# PCIE_Connector.net
KiCad netlist of a schematic drawn in Altium Designer
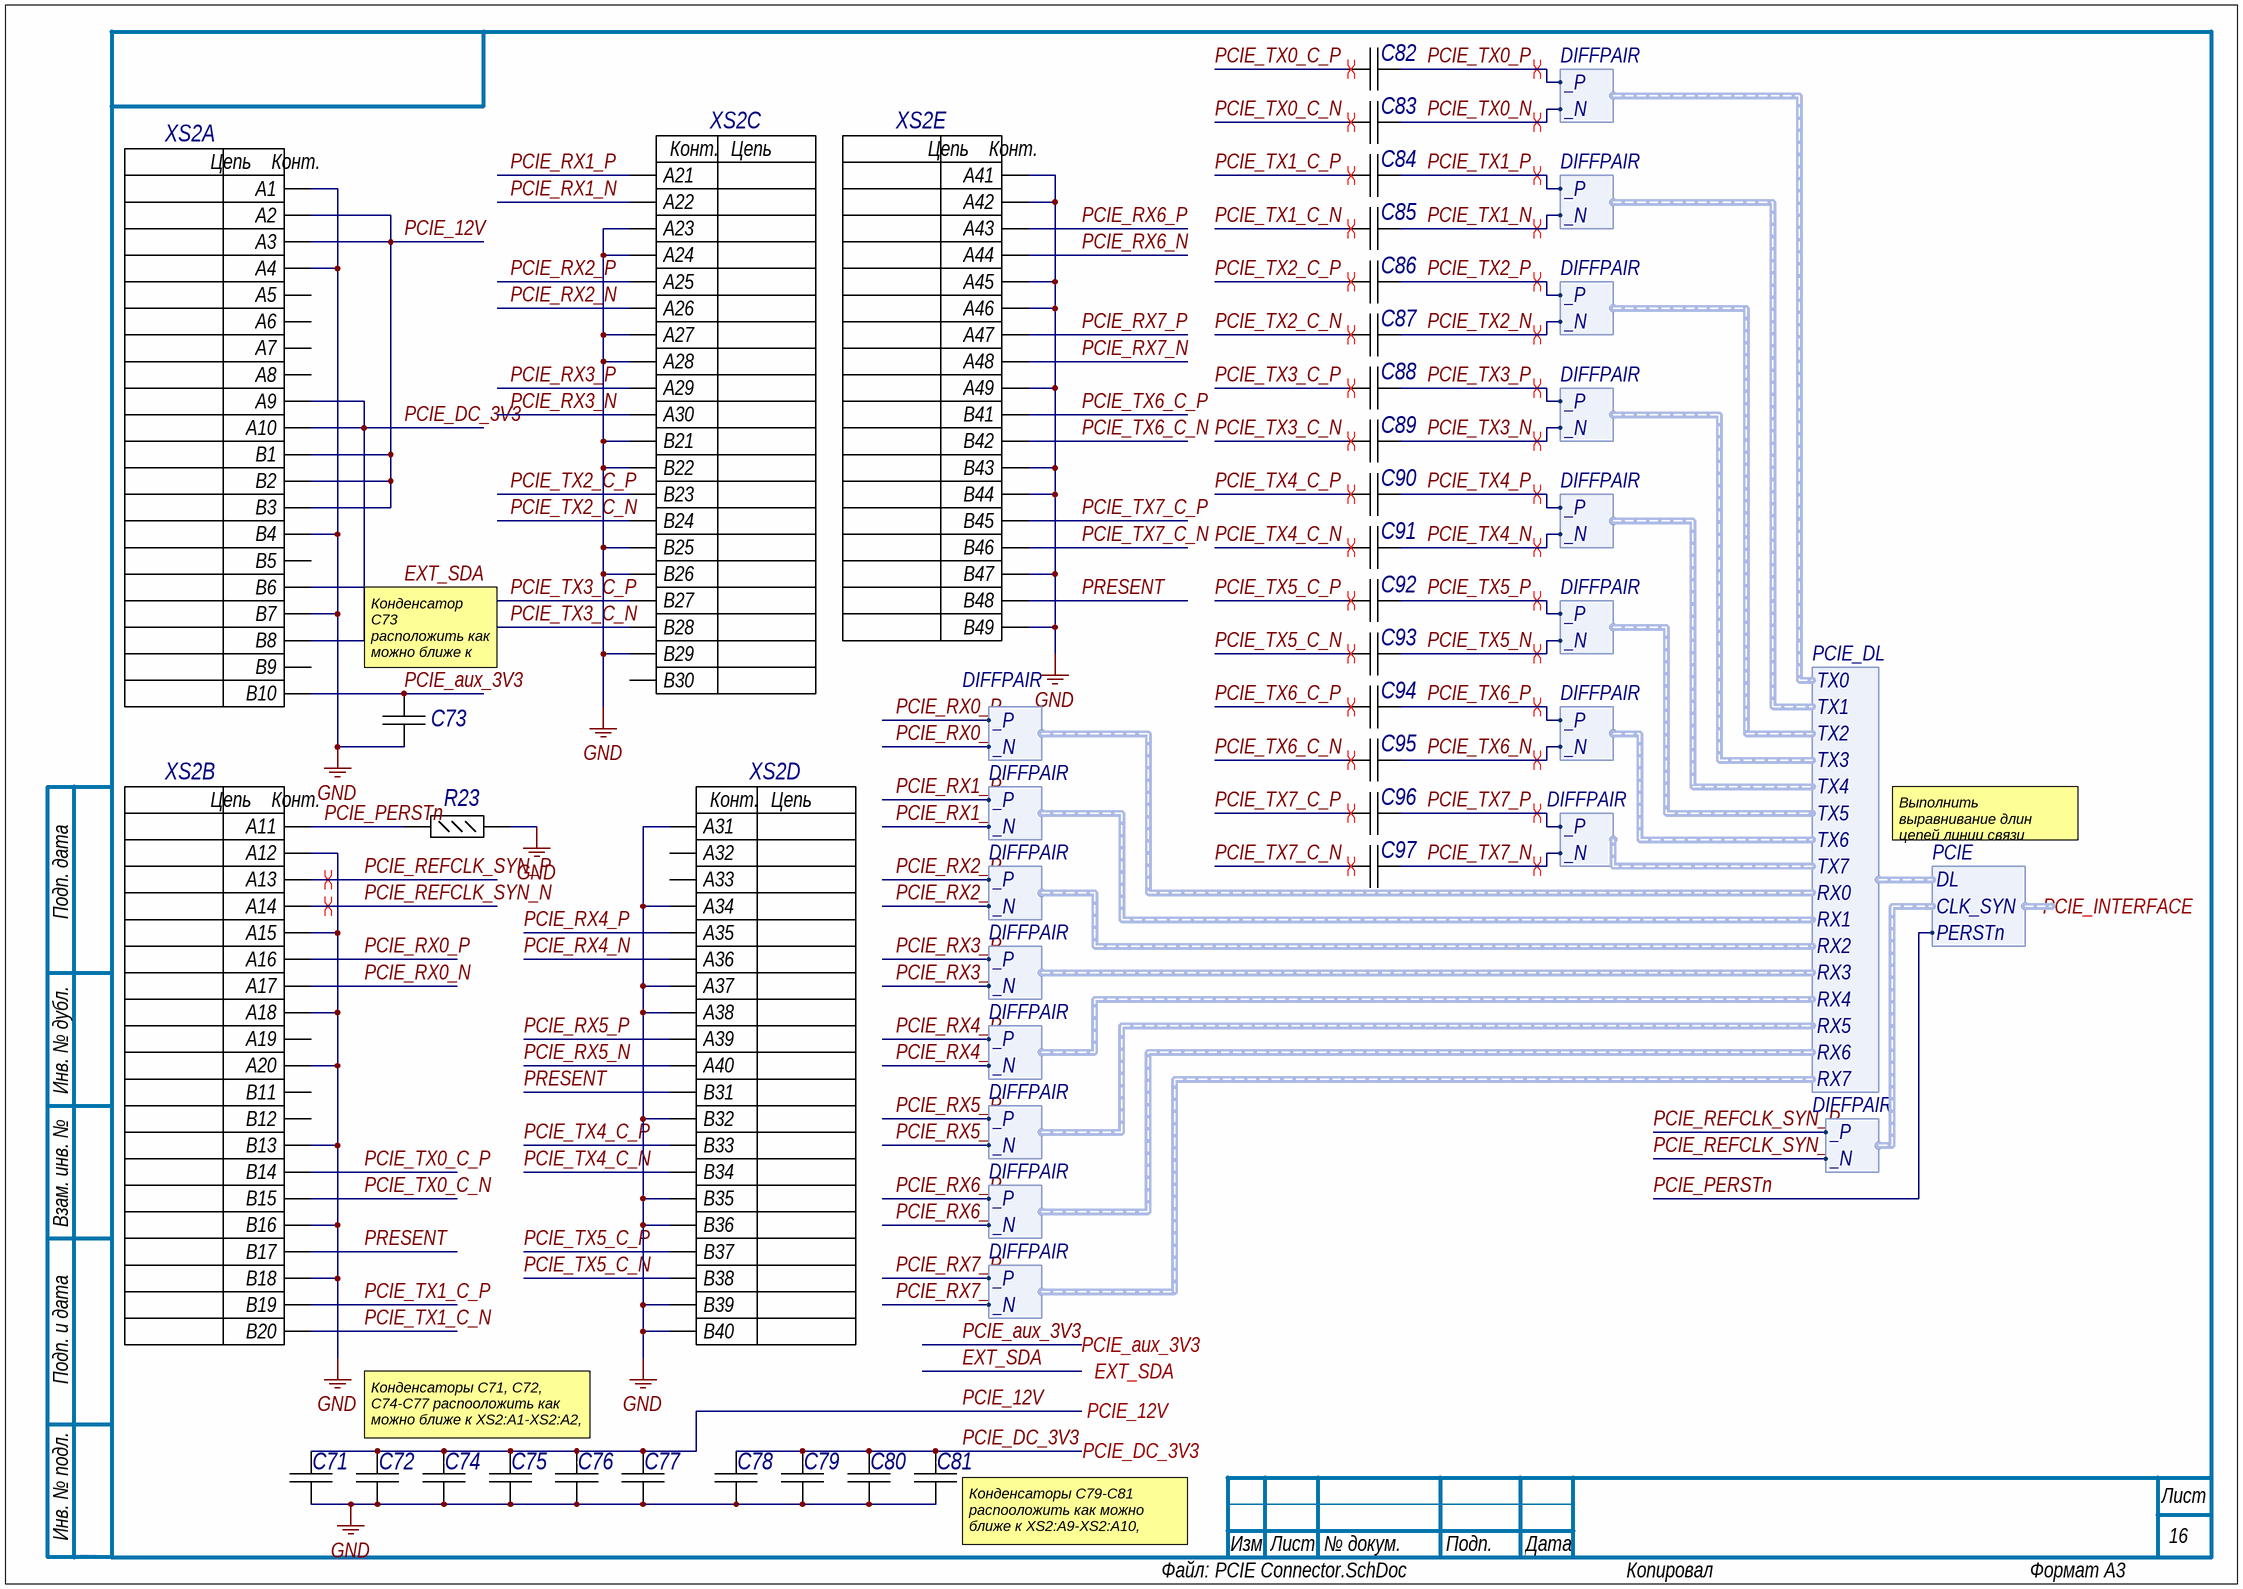
[diagram p0: PCIE Connector.SchDoc]

(export (version "E")
  (design (tool "Eeschema 10.0.6"))
  (components
    (comp (ref "C71")
      (value "GRM31CR61E226KE15L")
      (footprint "CAPC3216X180X55ML20T25")
      (description "Chip Capacitor, 22 uF, +/- 10%, 25 V, -55 to 85 degC, 1206 (3216 Metric), RoHS, Tape and Reel")
      (fields (field (name "TOLERANCE") "10%"))
      (libsource (lib "MiniPC DB") (part "CAP_NP"))
    )
    (comp (ref "C72")
      (value "C1005X7R1E104M")
      (footprint "CAPC1005X55X10LL05")
      (description "Chip Capacitor, 0.1 uF, +/- 20%, 25 V, -55 to 125 degC, 0402 (1005 Metric), RoHS, Tape and Reel")
      (fields (field (name "TOLERANCE") "20%"))
      (libsource (lib "MiniPC DB") (part "CAP_NP"))
    )
    (comp (ref "C73")
      (value "C1005X7R1E104M")
      (footprint "CAPC1005X55X10LL05")
      (description "Chip Capacitor, 0.1 uF, +/- 20%, 25 V, -55 to 125 degC, 0402 (1005 Metric), RoHS, Tape and Reel")
      (fields (field (name "TOLERANCE") "20%"))
      (libsource (lib "MiniPC DB") (part "CAP_NP"))
    )
    (comp (ref "C74")
      (value "C1005X7R1E104M")
      (footprint "CAPC1005X55X10LL05")
      (description "Chip Capacitor, 0.1 uF, +/- 20%, 25 V, -55 to 125 degC, 0402 (1005 Metric), RoHS, Tape and Reel")
      (fields (field (name "TOLERANCE") "20%"))
      (libsource (lib "MiniPC DB") (part "CAP_NP"))
    )
    (comp (ref "C75")
      (value "C1005X7R1E104M")
      (footprint "CAPC1005X55X10LL05")
      (description "Chip Capacitor, 0.1 uF, +/- 20%, 25 V, -55 to 125 degC, 0402 (1005 Metric), RoHS, Tape and Reel")
      (fields (field (name "TOLERANCE") "20%"))
      (libsource (lib "MiniPC DB") (part "CAP_NP"))
    )
    (comp (ref "C76")
      (value "C1005X7R1E104M")
      (footprint "CAPC1005X55X10LL05")
      (description "Chip Capacitor, 0.1 uF, +/- 20%, 25 V, -55 to 125 degC, 0402 (1005 Metric), RoHS, Tape and Reel")
      (fields (field (name "TOLERANCE") "20%"))
      (libsource (lib "MiniPC DB") (part "CAP_NP"))
    )
    (comp (ref "C77")
      (value "C1005X7R1E104M")
      (footprint "CAPC1005X55X10LL05")
      (description "Chip Capacitor, 0.1 uF, +/- 20%, 25 V, -55 to 125 degC, 0402 (1005 Metric), RoHS, Tape and Reel")
      (fields (field (name "TOLERANCE") "20%"))
      (libsource (lib "MiniPC DB") (part "CAP_NP"))
    )
    (comp (ref "C78")
      (value "C1005X7R1E104M")
      (footprint "CAPC1005X55X10LL05")
      (description "Chip Capacitor, 0.1 uF, +/- 20%, 25 V, -55 to 125 degC, 0402 (1005 Metric), RoHS, Tape and Reel")
      (fields (field (name "TOLERANCE") "20%"))
      (libsource (lib "MiniPC DB") (part "CAP_NP"))
    )
    (comp (ref "C79")
      (value "C1005X7R1E104M")
      (footprint "CAPC1005X55X10LL05")
      (description "Chip Capacitor, 0.1 uF, +/- 20%, 25 V, -55 to 125 degC, 0402 (1005 Metric), RoHS, Tape and Reel")
      (fields (field (name "TOLERANCE") "20%"))
      (libsource (lib "MiniPC DB") (part "CAP_NP"))
    )
    (comp (ref "C80")
      (value "C1005X7R1E104M")
      (footprint "CAPC1005X55X10LL05")
      (description "Chip Capacitor, 0.1 uF, +/- 20%, 25 V, -55 to 125 degC, 0402 (1005 Metric), RoHS, Tape and Reel")
      (fields (field (name "TOLERANCE") "20%"))
      (libsource (lib "MiniPC DB") (part "CAP_NP"))
    )
    (comp (ref "C81")
      (value "GRM31CR60J107ME39L")
      (footprint "CAPC3216X190X55ML30T25")
      (description "Chip Capacitor, 100 uF, +/- 20%, 6.3 V, -55 to 85 degC, 1206 (3216 Metric), RoHS, Tape and Reel")
      (fields (field (name "TOLERANCE") "20%"))
      (libsource (lib "MiniPC DB") (part "CAP_NP"))
    )
    (comp (ref "C82")
      (value "GRM155R61A224KE19D")
      (footprint "CAPC1005X55X25NL05T10")
      (description "Chip Capacitor, 220 nF, +/- 10%, 10 V, -55 to 85 degC, 0402 (1005 Metric), RoHS, Tape and Reel")
      (fields (field (name "TOLERANCE") "10%") (field (name "MANUFACTURER") "Basic Passives"))
      (libsource (lib "MiniPC DB") (part "CAP_NP"))
    )
    (comp (ref "C83")
      (value "GRM155R61A224KE19D")
      (footprint "CAPC1005X55X25NL05T10")
      (description "Chip Capacitor, 220 nF, +/- 10%, 10 V, -55 to 85 degC, 0402 (1005 Metric), RoHS, Tape and Reel")
      (fields (field (name "TOLERANCE") "10%") (field (name "MANUFACTURER") "Basic Passives"))
      (libsource (lib "MiniPC DB") (part "CAP_NP"))
    )
    (comp (ref "C84")
      (value "GRM155R61A224KE19D")
      (footprint "CAPC1005X55X25NL05T10")
      (description "Chip Capacitor, 220 nF, +/- 10%, 10 V, -55 to 85 degC, 0402 (1005 Metric), RoHS, Tape and Reel")
      (fields (field (name "TOLERANCE") "10%") (field (name "MANUFACTURER") "Basic Passives"))
      (libsource (lib "MiniPC DB") (part "CAP_NP"))
    )
    (comp (ref "C85")
      (value "GRM155R61A224KE19D")
      (footprint "CAPC1005X55X25NL05T10")
      (description "Chip Capacitor, 220 nF, +/- 10%, 10 V, -55 to 85 degC, 0402 (1005 Metric), RoHS, Tape and Reel")
      (fields (field (name "TOLERANCE") "10%") (field (name "MANUFACTURER") "Basic Passives"))
      (libsource (lib "MiniPC DB") (part "CAP_NP"))
    )
    (comp (ref "C86")
      (value "GRM155R61A224KE19D")
      (footprint "CAPC1005X55X25NL05T10")
      (description "Chip Capacitor, 220 nF, +/- 10%, 10 V, -55 to 85 degC, 0402 (1005 Metric), RoHS, Tape and Reel")
      (fields (field (name "TOLERANCE") "10%") (field (name "MANUFACTURER") "Basic Passives"))
      (libsource (lib "MiniPC DB") (part "CAP_NP"))
    )
    (comp (ref "C87")
      (value "GRM155R61A224KE19D")
      (footprint "CAPC1005X55X25NL05T10")
      (description "Chip Capacitor, 220 nF, +/- 10%, 10 V, -55 to 85 degC, 0402 (1005 Metric), RoHS, Tape and Reel")
      (fields (field (name "TOLERANCE") "10%") (field (name "MANUFACTURER") "Basic Passives"))
      (libsource (lib "MiniPC DB") (part "CAP_NP"))
    )
    (comp (ref "C88")
      (value "GRM155R61A224KE19D")
      (footprint "CAPC1005X55X25NL05T10")
      (description "Chip Capacitor, 220 nF, +/- 10%, 10 V, -55 to 85 degC, 0402 (1005 Metric), RoHS, Tape and Reel")
      (fields (field (name "TOLERANCE") "10%") (field (name "MANUFACTURER") "Basic Passives"))
      (libsource (lib "MiniPC DB") (part "CAP_NP"))
    )
    (comp (ref "C89")
      (value "GRM155R61A224KE19D")
      (footprint "CAPC1005X55X25NL05T10")
      (description "Chip Capacitor, 220 nF, +/- 10%, 10 V, -55 to 85 degC, 0402 (1005 Metric), RoHS, Tape and Reel")
      (fields (field (name "TOLERANCE") "10%") (field (name "MANUFACTURER") "Basic Passives"))
      (libsource (lib "MiniPC DB") (part "CAP_NP"))
    )
    (comp (ref "C90")
      (value "GRM155R61A224KE19D")
      (footprint "CAPC1005X55X25NL05T10")
      (description "Chip Capacitor, 220 nF, +/- 10%, 10 V, -55 to 85 degC, 0402 (1005 Metric), RoHS, Tape and Reel")
      (fields (field (name "TOLERANCE") "10%") (field (name "MANUFACTURER") "Basic Passives"))
      (libsource (lib "MiniPC DB") (part "CAP_NP"))
    )
    (comp (ref "C91")
      (value "GRM155R61A224KE19D")
      (footprint "CAPC1005X55X25NL05T10")
      (description "Chip Capacitor, 220 nF, +/- 10%, 10 V, -55 to 85 degC, 0402 (1005 Metric), RoHS, Tape and Reel")
      (fields (field (name "TOLERANCE") "10%") (field (name "MANUFACTURER") "Basic Passives"))
      (libsource (lib "MiniPC DB") (part "CAP_NP"))
    )
    (comp (ref "C92")
      (value "GRM155R61A224KE19D")
      (footprint "CAPC1005X55X25NL05T10")
      (description "Chip Capacitor, 220 nF, +/- 10%, 10 V, -55 to 85 degC, 0402 (1005 Metric), RoHS, Tape and Reel")
      (fields (field (name "TOLERANCE") "10%") (field (name "MANUFACTURER") "Basic Passives"))
      (libsource (lib "MiniPC DB") (part "CAP_NP"))
    )
    (comp (ref "C93")
      (value "GRM155R61A224KE19D")
      (footprint "CAPC1005X55X25NL05T10")
      (description "Chip Capacitor, 220 nF, +/- 10%, 10 V, -55 to 85 degC, 0402 (1005 Metric), RoHS, Tape and Reel")
      (fields (field (name "TOLERANCE") "10%") (field (name "MANUFACTURER") "Basic Passives"))
      (libsource (lib "MiniPC DB") (part "CAP_NP"))
    )
    (comp (ref "C94")
      (value "GRM155R61A224KE19D")
      (footprint "CAPC1005X55X25NL05T10")
      (description "Chip Capacitor, 220 nF, +/- 10%, 10 V, -55 to 85 degC, 0402 (1005 Metric), RoHS, Tape and Reel")
      (fields (field (name "TOLERANCE") "10%") (field (name "MANUFACTURER") "Basic Passives"))
      (libsource (lib "MiniPC DB") (part "CAP_NP"))
    )
    (comp (ref "C95")
      (value "GRM155R61A224KE19D")
      (footprint "CAPC1005X55X25NL05T10")
      (description "Chip Capacitor, 220 nF, +/- 10%, 10 V, -55 to 85 degC, 0402 (1005 Metric), RoHS, Tape and Reel")
      (fields (field (name "TOLERANCE") "10%") (field (name "MANUFACTURER") "Basic Passives"))
      (libsource (lib "MiniPC DB") (part "CAP_NP"))
    )
    (comp (ref "C96")
      (value "GRM155R61A224KE19D")
      (footprint "CAPC1005X55X25NL05T10")
      (description "Chip Capacitor, 220 nF, +/- 10%, 10 V, -55 to 85 degC, 0402 (1005 Metric), RoHS, Tape and Reel")
      (fields (field (name "TOLERANCE") "10%") (field (name "MANUFACTURER") "Basic Passives"))
      (libsource (lib "MiniPC DB") (part "CAP_NP"))
    )
    (comp (ref "C97")
      (value "GRM155R61A224KE19D")
      (footprint "CAPC1005X55X25NL05T10")
      (description "Chip Capacitor, 220 nF, +/- 10%, 10 V, -55 to 85 degC, 0402 (1005 Metric), RoHS, Tape and Reel")
      (fields (field (name "TOLERANCE") "10%") (field (name "MANUFACTURER") "Basic Passives"))
      (libsource (lib "MiniPC DB") (part "CAP_NP"))
    )
    (comp (ref "R23")
      (value "ERJ-2RKF4701X")
      (footprint "RESC1005X40X25LL05T05")
      (description "Chip Resistor, 4.7 KOhm, +/- 1%, 0.1 W, -55 to 155 degC, 0402 (1005 Metric), RoHS, Tape and Reel")
      (fields (field (name "TOLERANCE") "1%"))
      (libsource (lib "MiniPC DB") (part "RES-0.05"))
    )
    (comp (ref "XS2")
      (value "PCIE-098-02-F-D-TH")
      (footprint "SMTC-PCIE-098-02-F-D-TH_V")
      (fields (field (name "MANUFACTURER") "Samtec"))
      (libsource (lib "MiniPC DB") (part "PCIE-098-02-F-D-TH"))
    )
  )
  (nets
    (net (code "3") (name "/EXT_SDA") (class "Default")
      (node (ref "XS2") (pin "B6") (pinfunction "B6_B6") (pintype "passive"))
    )
    (net (code "4") (name "/PCIE_12V") (class "Default")
      (node (ref "C71") (pin "2") (pinfunction "2_2") (pintype "passive"))
      (node (ref "C72") (pin "2") (pinfunction "2_2") (pintype "passive"))
      (node (ref "C74") (pin "2") (pinfunction "2_2") (pintype "passive"))
      (node (ref "C75") (pin "2") (pinfunction "2_2") (pintype "passive"))
      (node (ref "C76") (pin "2") (pinfunction "2_2") (pintype "passive"))
      (node (ref "C77") (pin "2") (pinfunction "2_2") (pintype "passive"))
      (node (ref "XS2") (pin "A2") (pinfunction "A2_A2") (pintype "passive"))
      (node (ref "XS2") (pin "A3") (pinfunction "A3_A3") (pintype "passive"))
      (node (ref "XS2") (pin "B1") (pinfunction "B1_B1") (pintype "passive"))
      (node (ref "XS2") (pin "B2") (pinfunction "B2_B2") (pintype "passive"))
      (node (ref "XS2") (pin "B3") (pinfunction "B3_B3") (pintype "passive"))
    )
    (net (code "5") (name "/PCIE_DC_3V3") (class "Default")
      (node (ref "C78") (pin "2") (pinfunction "2_2") (pintype "passive"))
      (node (ref "C79") (pin "2") (pinfunction "2_2") (pintype "passive"))
      (node (ref "C80") (pin "2") (pinfunction "2_2") (pintype "passive"))
      (node (ref "C81") (pin "2") (pinfunction "2_2") (pintype "passive"))
      (node (ref "XS2") (pin "A10") (pinfunction "A10_A10") (pintype "passive"))
      (node (ref "XS2") (pin "A9") (pinfunction "A9_A9") (pintype "passive"))
      (node (ref "XS2") (pin "B8") (pinfunction "B8_B8") (pintype "passive"))
    )
    (net (code "6") (name "/PCIE_PERSTn") (class "Default")
      (node (ref "R23") (pin "1") (pinfunction "1_1") (pintype "passive"))
      (node (ref "XS2") (pin "A11") (pinfunction "A11_A11") (pintype "passive"))
    )
    (net (code "7") (name "/PCIE_REFCLK_SYN_N") (class "Default")
      (node (ref "XS2") (pin "A14") (pinfunction "A14_A14") (pintype "passive"))
    )
    (net (code "8") (name "/PCIE_REFCLK_SYN_P") (class "Default")
      (node (ref "XS2") (pin "A13") (pinfunction "A13_A13") (pintype "passive"))
    )
    (net (code "9") (name "/PCIE_RX0_N") (class "Default")
      (node (ref "XS2") (pin "A17") (pinfunction "A17_A17") (pintype "passive"))
    )
    (net (code "10") (name "/PCIE_RX0_P") (class "Default")
      (node (ref "XS2") (pin "A16") (pinfunction "A16_A16") (pintype "passive"))
    )
    (net (code "11") (name "/PCIE_RX1_N") (class "Default")
      (node (ref "XS2") (pin "A22") (pinfunction "A22_A22") (pintype "passive"))
    )
    (net (code "12") (name "/PCIE_RX1_P") (class "Default")
      (node (ref "XS2") (pin "A21") (pinfunction "A21_A21") (pintype "passive"))
    )
    (net (code "13") (name "/PCIE_RX2_N") (class "Default")
      (node (ref "XS2") (pin "A26") (pinfunction "A26_A26") (pintype "passive"))
    )
    (net (code "14") (name "/PCIE_RX2_P") (class "Default")
      (node (ref "XS2") (pin "A25") (pinfunction "A25_A25") (pintype "passive"))
    )
    (net (code "15") (name "/PCIE_RX3_N") (class "Default")
      (node (ref "XS2") (pin "A30") (pinfunction "A30_A30") (pintype "passive"))
    )
    (net (code "16") (name "/PCIE_RX3_P") (class "Default")
      (node (ref "XS2") (pin "A29") (pinfunction "A29_A29") (pintype "passive"))
    )
    (net (code "17") (name "/PCIE_RX4_N") (class "Default")
      (node (ref "XS2") (pin "A36") (pinfunction "A36_A36") (pintype "passive"))
    )
    (net (code "18") (name "/PCIE_RX4_P") (class "Default")
      (node (ref "XS2") (pin "A35") (pinfunction "A35_A35") (pintype "passive"))
    )
    (net (code "19") (name "/PCIE_RX5_N") (class "Default")
      (node (ref "XS2") (pin "A40") (pinfunction "A40_A40") (pintype "passive"))
    )
    (net (code "20") (name "/PCIE_RX5_P") (class "Default")
      (node (ref "XS2") (pin "A39") (pinfunction "A39_A39") (pintype "passive"))
    )
    (net (code "21") (name "/PCIE_RX6_N") (class "Default")
      (node (ref "XS2") (pin "A44") (pinfunction "A44_A44") (pintype "passive"))
    )
    (net (code "22") (name "/PCIE_RX6_P") (class "Default")
      (node (ref "XS2") (pin "A43") (pinfunction "A43_A43") (pintype "passive"))
    )
    (net (code "23") (name "/PCIE_RX7_N") (class "Default")
      (node (ref "XS2") (pin "A48") (pinfunction "A48_A48") (pintype "passive"))
    )
    (net (code "24") (name "/PCIE_RX7_P") (class "Default")
      (node (ref "XS2") (pin "A47") (pinfunction "A47_A47") (pintype "passive"))
    )
    (net (code "25") (name "/PCIE_TX0_C_N") (class "Default")
      (node (ref "C83") (pin "2") (pinfunction "2_2") (pintype "passive"))
      (node (ref "XS2") (pin "B15") (pinfunction "B15_B15") (pintype "passive"))
    )
    (net (code "26") (name "/PCIE_TX0_C_P") (class "Default")
      (node (ref "C82") (pin "2") (pinfunction "2_2") (pintype "passive"))
      (node (ref "XS2") (pin "B14") (pinfunction "B14_B14") (pintype "passive"))
    )
    (net (code "27") (name "/PCIE_TX0_N") (class "Default")
      (node (ref "C83") (pin "1") (pinfunction "1_1") (pintype "passive"))
    )
    (net (code "28") (name "/PCIE_TX0_P") (class "Default")
      (node (ref "C82") (pin "1") (pinfunction "1_1") (pintype "passive"))
    )
    (net (code "29") (name "/PCIE_TX1_C_N") (class "Default")
      (node (ref "C85") (pin "2") (pinfunction "2_2") (pintype "passive"))
      (node (ref "XS2") (pin "B20") (pinfunction "B20_B20") (pintype "passive"))
    )
    (net (code "30") (name "/PCIE_TX1_C_P") (class "Default")
      (node (ref "C84") (pin "2") (pinfunction "2_2") (pintype "passive"))
      (node (ref "XS2") (pin "B19") (pinfunction "B19_B19") (pintype "passive"))
    )
    (net (code "31") (name "/PCIE_TX1_N") (class "Default")
      (node (ref "C85") (pin "1") (pinfunction "1_1") (pintype "passive"))
    )
    (net (code "32") (name "/PCIE_TX1_P") (class "Default")
      (node (ref "C84") (pin "1") (pinfunction "1_1") (pintype "passive"))
    )
    (net (code "33") (name "/PCIE_TX2_C_N") (class "Default")
      (node (ref "C87") (pin "2") (pinfunction "2_2") (pintype "passive"))
      (node (ref "XS2") (pin "B24") (pinfunction "B24_B24") (pintype "passive"))
    )
    (net (code "34") (name "/PCIE_TX2_C_P") (class "Default")
      (node (ref "C86") (pin "2") (pinfunction "2_2") (pintype "passive"))
      (node (ref "XS2") (pin "B23") (pinfunction "B23_B23") (pintype "passive"))
    )
    (net (code "35") (name "/PCIE_TX2_N") (class "Default")
      (node (ref "C87") (pin "1") (pinfunction "1_1") (pintype "passive"))
    )
    (net (code "36") (name "/PCIE_TX2_P") (class "Default")
      (node (ref "C86") (pin "1") (pinfunction "1_1") (pintype "passive"))
    )
    (net (code "37") (name "/PCIE_TX3_C_N") (class "Default")
      (node (ref "C89") (pin "2") (pinfunction "2_2") (pintype "passive"))
      (node (ref "XS2") (pin "B28") (pinfunction "B28_B28") (pintype "passive"))
    )
    (net (code "38") (name "/PCIE_TX3_C_P") (class "Default")
      (node (ref "C88") (pin "2") (pinfunction "2_2") (pintype "passive"))
      (node (ref "XS2") (pin "B27") (pinfunction "B27_B27") (pintype "passive"))
    )
    (net (code "39") (name "/PCIE_TX3_N") (class "Default")
      (node (ref "C89") (pin "1") (pinfunction "1_1") (pintype "passive"))
    )
    (net (code "40") (name "/PCIE_TX3_P") (class "Default")
      (node (ref "C88") (pin "1") (pinfunction "1_1") (pintype "passive"))
    )
    (net (code "41") (name "/PCIE_TX4_C_N") (class "Default")
      (node (ref "C91") (pin "2") (pinfunction "2_2") (pintype "passive"))
      (node (ref "XS2") (pin "B34") (pinfunction "B34_B34") (pintype "passive"))
    )
    (net (code "42") (name "/PCIE_TX4_C_P") (class "Default")
      (node (ref "C90") (pin "2") (pinfunction "2_2") (pintype "passive"))
      (node (ref "XS2") (pin "B33") (pinfunction "B33_B33") (pintype "passive"))
    )
    (net (code "43") (name "/PCIE_TX4_N") (class "Default")
      (node (ref "C91") (pin "1") (pinfunction "1_1") (pintype "passive"))
    )
    (net (code "44") (name "/PCIE_TX4_P") (class "Default")
      (node (ref "C90") (pin "1") (pinfunction "1_1") (pintype "passive"))
    )
    (net (code "45") (name "/PCIE_TX5_C_N") (class "Default")
      (node (ref "C93") (pin "2") (pinfunction "2_2") (pintype "passive"))
      (node (ref "XS2") (pin "B38") (pinfunction "B38_B38") (pintype "passive"))
    )
    (net (code "46") (name "/PCIE_TX5_C_P") (class "Default")
      (node (ref "C92") (pin "2") (pinfunction "2_2") (pintype "passive"))
      (node (ref "XS2") (pin "B37") (pinfunction "B37_B37") (pintype "passive"))
    )
    (net (code "47") (name "/PCIE_TX5_N") (class "Default")
      (node (ref "C93") (pin "1") (pinfunction "1_1") (pintype "passive"))
    )
    (net (code "48") (name "/PCIE_TX5_P") (class "Default")
      (node (ref "C92") (pin "1") (pinfunction "1_1") (pintype "passive"))
    )
    (net (code "49") (name "/PCIE_TX6_C_N") (class "Default")
      (node (ref "C95") (pin "2") (pinfunction "2_2") (pintype "passive"))
      (node (ref "XS2") (pin "B42") (pinfunction "B42_B42") (pintype "passive"))
    )
    (net (code "50") (name "/PCIE_TX6_C_P") (class "Default")
      (node (ref "C94") (pin "2") (pinfunction "2_2") (pintype "passive"))
      (node (ref "XS2") (pin "B41") (pinfunction "B41_B41") (pintype "passive"))
    )
    (net (code "51") (name "/PCIE_TX6_N") (class "Default")
      (node (ref "C95") (pin "1") (pinfunction "1_1") (pintype "passive"))
    )
    (net (code "52") (name "/PCIE_TX6_P") (class "Default")
      (node (ref "C94") (pin "1") (pinfunction "1_1") (pintype "passive"))
    )
    (net (code "53") (name "/PCIE_TX7_C_N") (class "Default")
      (node (ref "C97") (pin "2") (pinfunction "2_2") (pintype "passive"))
      (node (ref "XS2") (pin "B46") (pinfunction "B46_B46") (pintype "passive"))
    )
    (net (code "54") (name "/PCIE_TX7_C_P") (class "Default")
      (node (ref "C96") (pin "2") (pinfunction "2_2") (pintype "passive"))
      (node (ref "XS2") (pin "B45") (pinfunction "B45_B45") (pintype "passive"))
    )
    (net (code "55") (name "/PCIE_TX7_N") (class "Default")
      (node (ref "C97") (pin "1") (pinfunction "1_1") (pintype "passive"))
    )
    (net (code "56") (name "/PCIE_TX7_P") (class "Default")
      (node (ref "C96") (pin "1") (pinfunction "1_1") (pintype "passive"))
    )
    (net (code "57") (name "/PCIE_aux_3V3") (class "Default")
      (node (ref "C73") (pin "2") (pinfunction "2_2") (pintype "passive"))
      (node (ref "XS2") (pin "B10") (pinfunction "B10_B10") (pintype "passive"))
    )
    (net (code "58") (name "/PRESENT") (class "Default")
      (node (ref "XS2") (pin "B17") (pinfunction "B17_B17") (pintype "passive"))
      (node (ref "XS2") (pin "B31") (pinfunction "B31_B31") (pintype "passive"))
      (node (ref "XS2") (pin "B48") (pinfunction "B48_B48") (pintype "passive"))
    )
    (net (code "61") (name "GND") (class "Default")
      (node (ref "C71") (pin "1") (pinfunction "1_1") (pintype "passive"))
      (node (ref "C72") (pin "1") (pinfunction "1_1") (pintype "passive"))
      (node (ref "C73") (pin "1") (pinfunction "1_1") (pintype "passive"))
      (node (ref "C74") (pin "1") (pinfunction "1_1") (pintype "passive"))
      (node (ref "C75") (pin "1") (pinfunction "1_1") (pintype "passive"))
      (node (ref "C76") (pin "1") (pinfunction "1_1") (pintype "passive"))
      (node (ref "C77") (pin "1") (pinfunction "1_1") (pintype "passive"))
      (node (ref "C78") (pin "1") (pinfunction "1_1") (pintype "passive"))
      (node (ref "C79") (pin "1") (pinfunction "1_1") (pintype "passive"))
      (node (ref "C80") (pin "1") (pinfunction "1_1") (pintype "passive"))
      (node (ref "C81") (pin "1") (pinfunction "1_1") (pintype "passive"))
      (node (ref "R23") (pin "2") (pinfunction "2_2") (pintype "passive"))
      (node (ref "XS2") (pin "A1") (pinfunction "A1_A1") (pintype "passive"))
      (node (ref "XS2") (pin "A12") (pinfunction "A12_A12") (pintype "passive"))
      (node (ref "XS2") (pin "A15") (pinfunction "A15_A15") (pintype "passive"))
      (node (ref "XS2") (pin "A18") (pinfunction "A18_A18") (pintype "passive"))
      (node (ref "XS2") (pin "A20") (pinfunction "A20_A20") (pintype "passive"))
      (node (ref "XS2") (pin "A23") (pinfunction "A23_A23") (pintype "passive"))
      (node (ref "XS2") (pin "A24") (pinfunction "A24_A24") (pintype "passive"))
      (node (ref "XS2") (pin "A27") (pinfunction "A27_A27") (pintype "passive"))
      (node (ref "XS2") (pin "A28") (pinfunction "A28_A28") (pintype "passive"))
      (node (ref "XS2") (pin "A31") (pinfunction "A31_A31") (pintype "passive"))
      (node (ref "XS2") (pin "A34") (pinfunction "A34_A34") (pintype "passive"))
      (node (ref "XS2") (pin "A37") (pinfunction "A37_A37") (pintype "passive"))
      (node (ref "XS2") (pin "A38") (pinfunction "A38_A38") (pintype "passive"))
      (node (ref "XS2") (pin "A4") (pinfunction "A4_A4") (pintype "passive"))
      (node (ref "XS2") (pin "A41") (pinfunction "A41_A41") (pintype "passive"))
      (node (ref "XS2") (pin "A42") (pinfunction "A42_A42") (pintype "passive"))
      (node (ref "XS2") (pin "A45") (pinfunction "A45_A45") (pintype "passive"))
      (node (ref "XS2") (pin "A46") (pinfunction "A46_A46") (pintype "passive"))
      (node (ref "XS2") (pin "A49") (pinfunction "A49_A49") (pintype "passive"))
      (node (ref "XS2") (pin "B13") (pinfunction "B13_B13") (pintype "passive"))
      (node (ref "XS2") (pin "B16") (pinfunction "B16_B16") (pintype "passive"))
      (node (ref "XS2") (pin "B18") (pinfunction "B18_B18") (pintype "passive"))
      (node (ref "XS2") (pin "B21") (pinfunction "B21_B21") (pintype "passive"))
      (node (ref "XS2") (pin "B22") (pinfunction "B22_B22") (pintype "passive"))
      (node (ref "XS2") (pin "B25") (pinfunction "B25_B25") (pintype "passive"))
      (node (ref "XS2") (pin "B26") (pinfunction "B26_B26") (pintype "passive"))
      (node (ref "XS2") (pin "B29") (pinfunction "B29_B29") (pintype "passive"))
      (node (ref "XS2") (pin "B32") (pinfunction "B32_B32") (pintype "passive"))
      (node (ref "XS2") (pin "B35") (pinfunction "B35_B35") (pintype "passive"))
      (node (ref "XS2") (pin "B36") (pinfunction "B36_B36") (pintype "passive"))
      (node (ref "XS2") (pin "B39") (pinfunction "B39_B39") (pintype "passive"))
      (node (ref "XS2") (pin "B4") (pinfunction "B4_B4") (pintype "passive"))
      (node (ref "XS2") (pin "B40") (pinfunction "B40_B40") (pintype "passive"))
      (node (ref "XS2") (pin "B43") (pinfunction "B43_B43") (pintype "passive"))
      (node (ref "XS2") (pin "B44") (pinfunction "B44_B44") (pintype "passive"))
      (node (ref "XS2") (pin "B47") (pinfunction "B47_B47") (pintype "passive"))
      (node (ref "XS2") (pin "B49") (pinfunction "B49_B49") (pintype "passive"))
      (node (ref "XS2") (pin "B7") (pinfunction "B7_B7") (pintype "passive"))
    )
    (net (code "62") (name "unconnected-(XS2-PadA5)") (class "Default")
      (node (ref "XS2") (pin "A5") (pinfunction "A5_A5") (pintype "passive"))
    )
    (net (code "63") (name "unconnected-(XS2-PadA6)") (class "Default")
      (node (ref "XS2") (pin "A6") (pinfunction "A6_A6") (pintype "passive"))
    )
    (net (code "64") (name "unconnected-(XS2-PadA7)") (class "Default")
      (node (ref "XS2") (pin "A7") (pinfunction "A7_A7") (pintype "passive"))
    )
    (net (code "65") (name "unconnected-(XS2-PadA8)") (class "Default")
      (node (ref "XS2") (pin "A8") (pinfunction "A8_A8") (pintype "passive"))
    )
    (net (code "66") (name "unconnected-(XS2-PadA19)") (class "Default")
      (node (ref "XS2") (pin "A19") (pinfunction "A19_A19") (pintype "passive"))
    )
    (net (code "67") (name "unconnected-(XS2-PadA32)") (class "Default")
      (node (ref "XS2") (pin "A32") (pinfunction "A32_A32") (pintype "passive"))
    )
    (net (code "68") (name "unconnected-(XS2-PadA33)") (class "Default")
      (node (ref "XS2") (pin "A33") (pinfunction "A33_A33") (pintype "passive"))
    )
    (net (code "69") (name "unconnected-(XS2-PadB5)") (class "Default")
      (node (ref "XS2") (pin "B5") (pinfunction "B5_B5") (pintype "passive"))
    )
    (net (code "70") (name "unconnected-(XS2-PadB9)") (class "Default")
      (node (ref "XS2") (pin "B9") (pinfunction "B9_B9") (pintype "passive"))
    )
    (net (code "71") (name "unconnected-(XS2-PadB11)") (class "Default")
      (node (ref "XS2") (pin "B11") (pinfunction "B11_B11") (pintype "passive"))
    )
    (net (code "72") (name "unconnected-(XS2-PadB12)") (class "Default")
      (node (ref "XS2") (pin "B12") (pinfunction "B12_B12") (pintype "passive"))
    )
    (net (code "73") (name "unconnected-(XS2-PadB30)") (class "Default")
      (node (ref "XS2") (pin "B30") (pinfunction "B30_B30") (pintype "passive"))
    )
  )
)
